# 00C-001.net
KiCad netlist of a schematic drawn in EAGLE
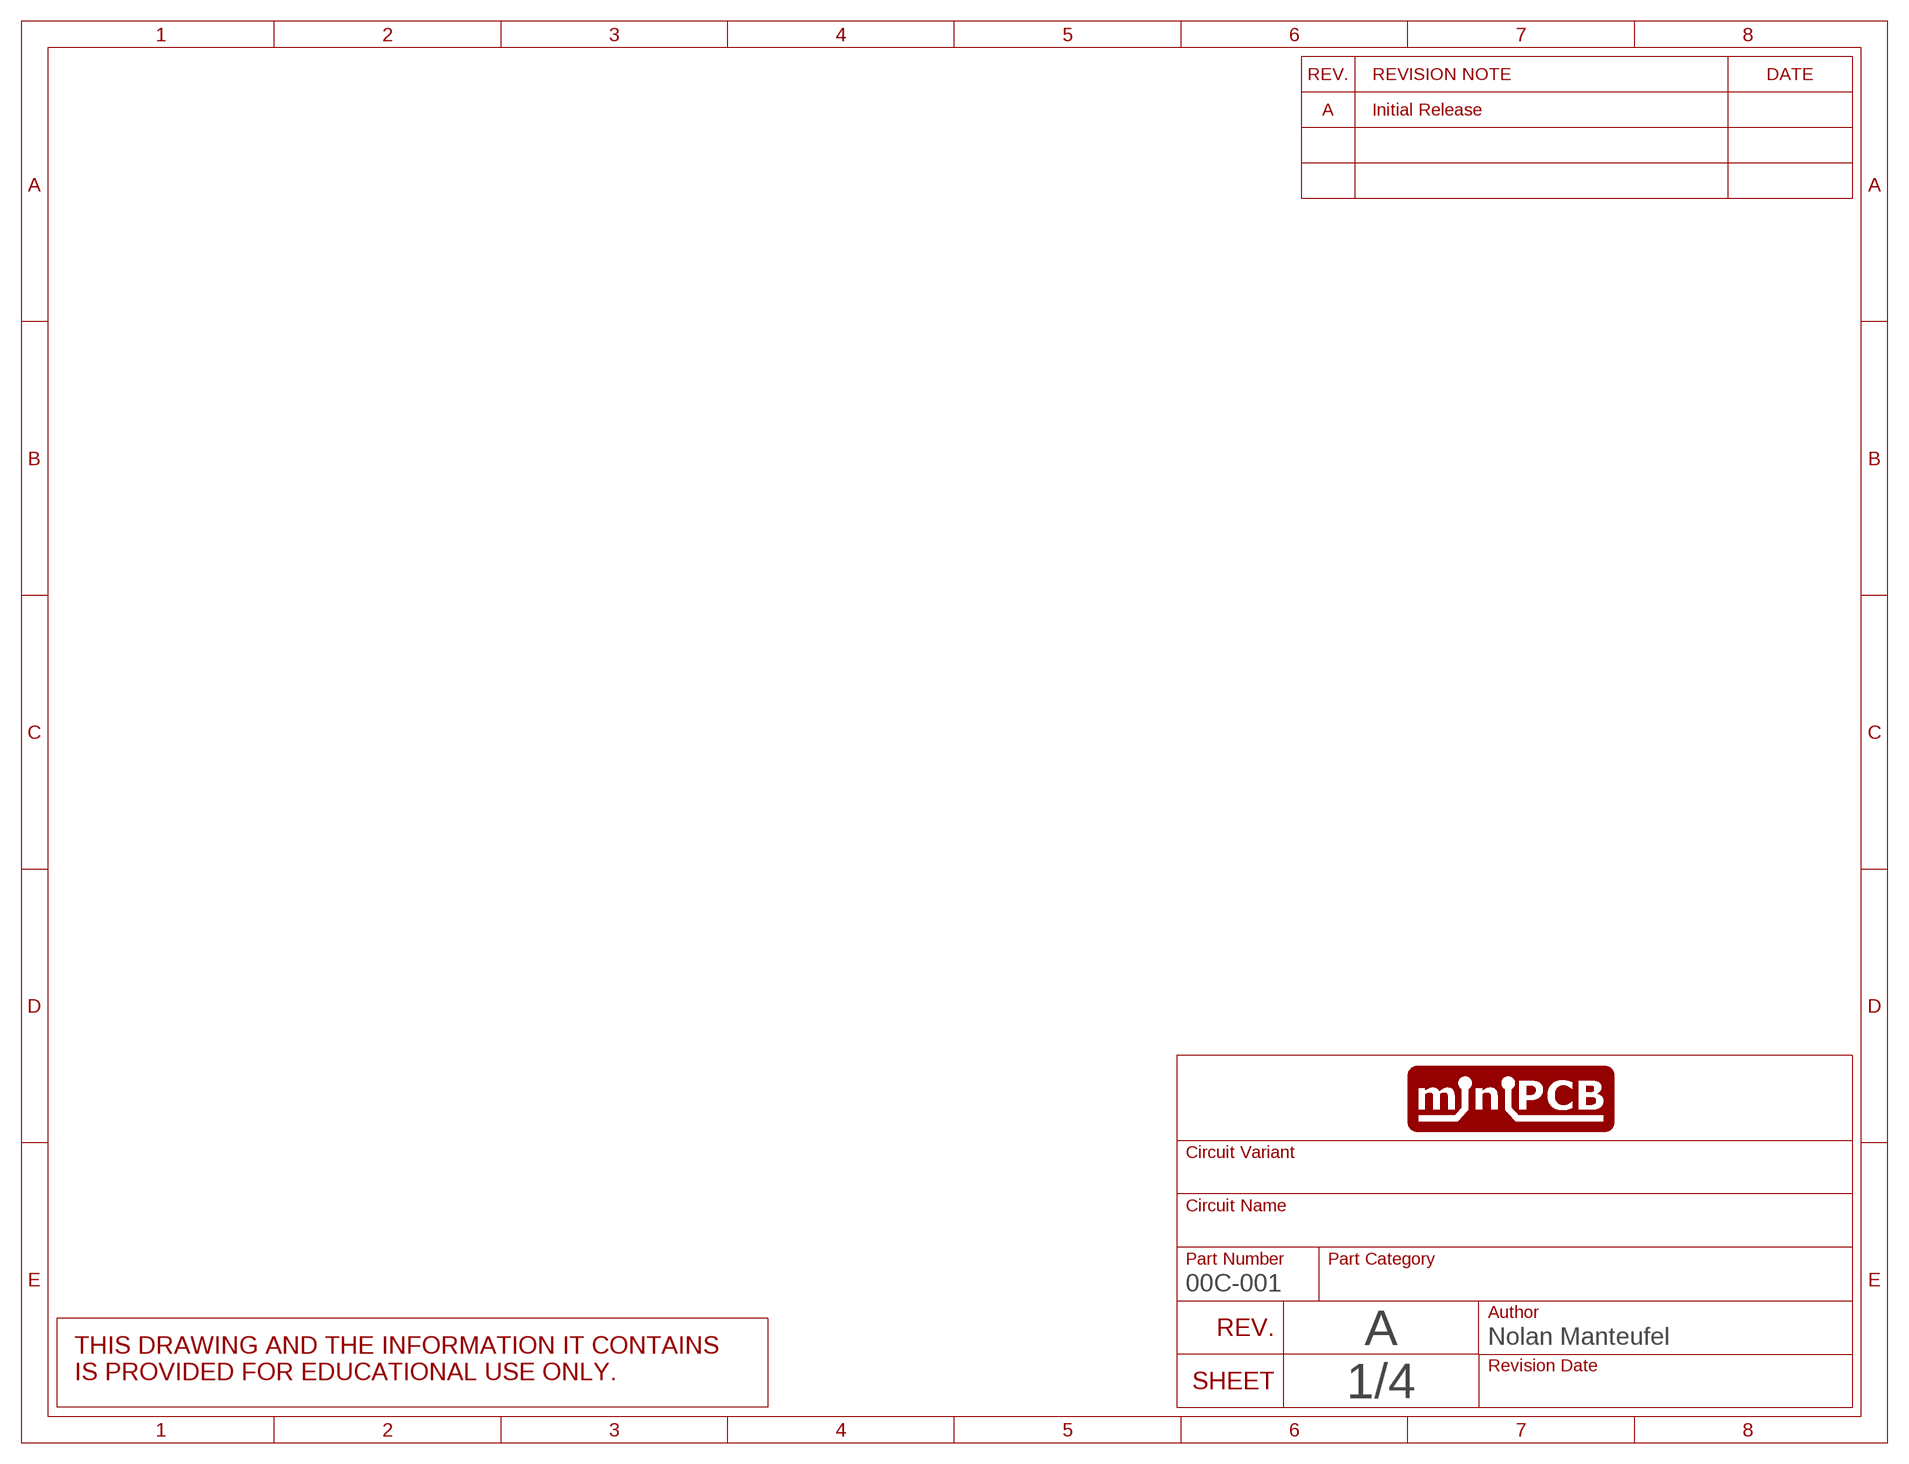
[diagram p0: schematic, sheet 1]
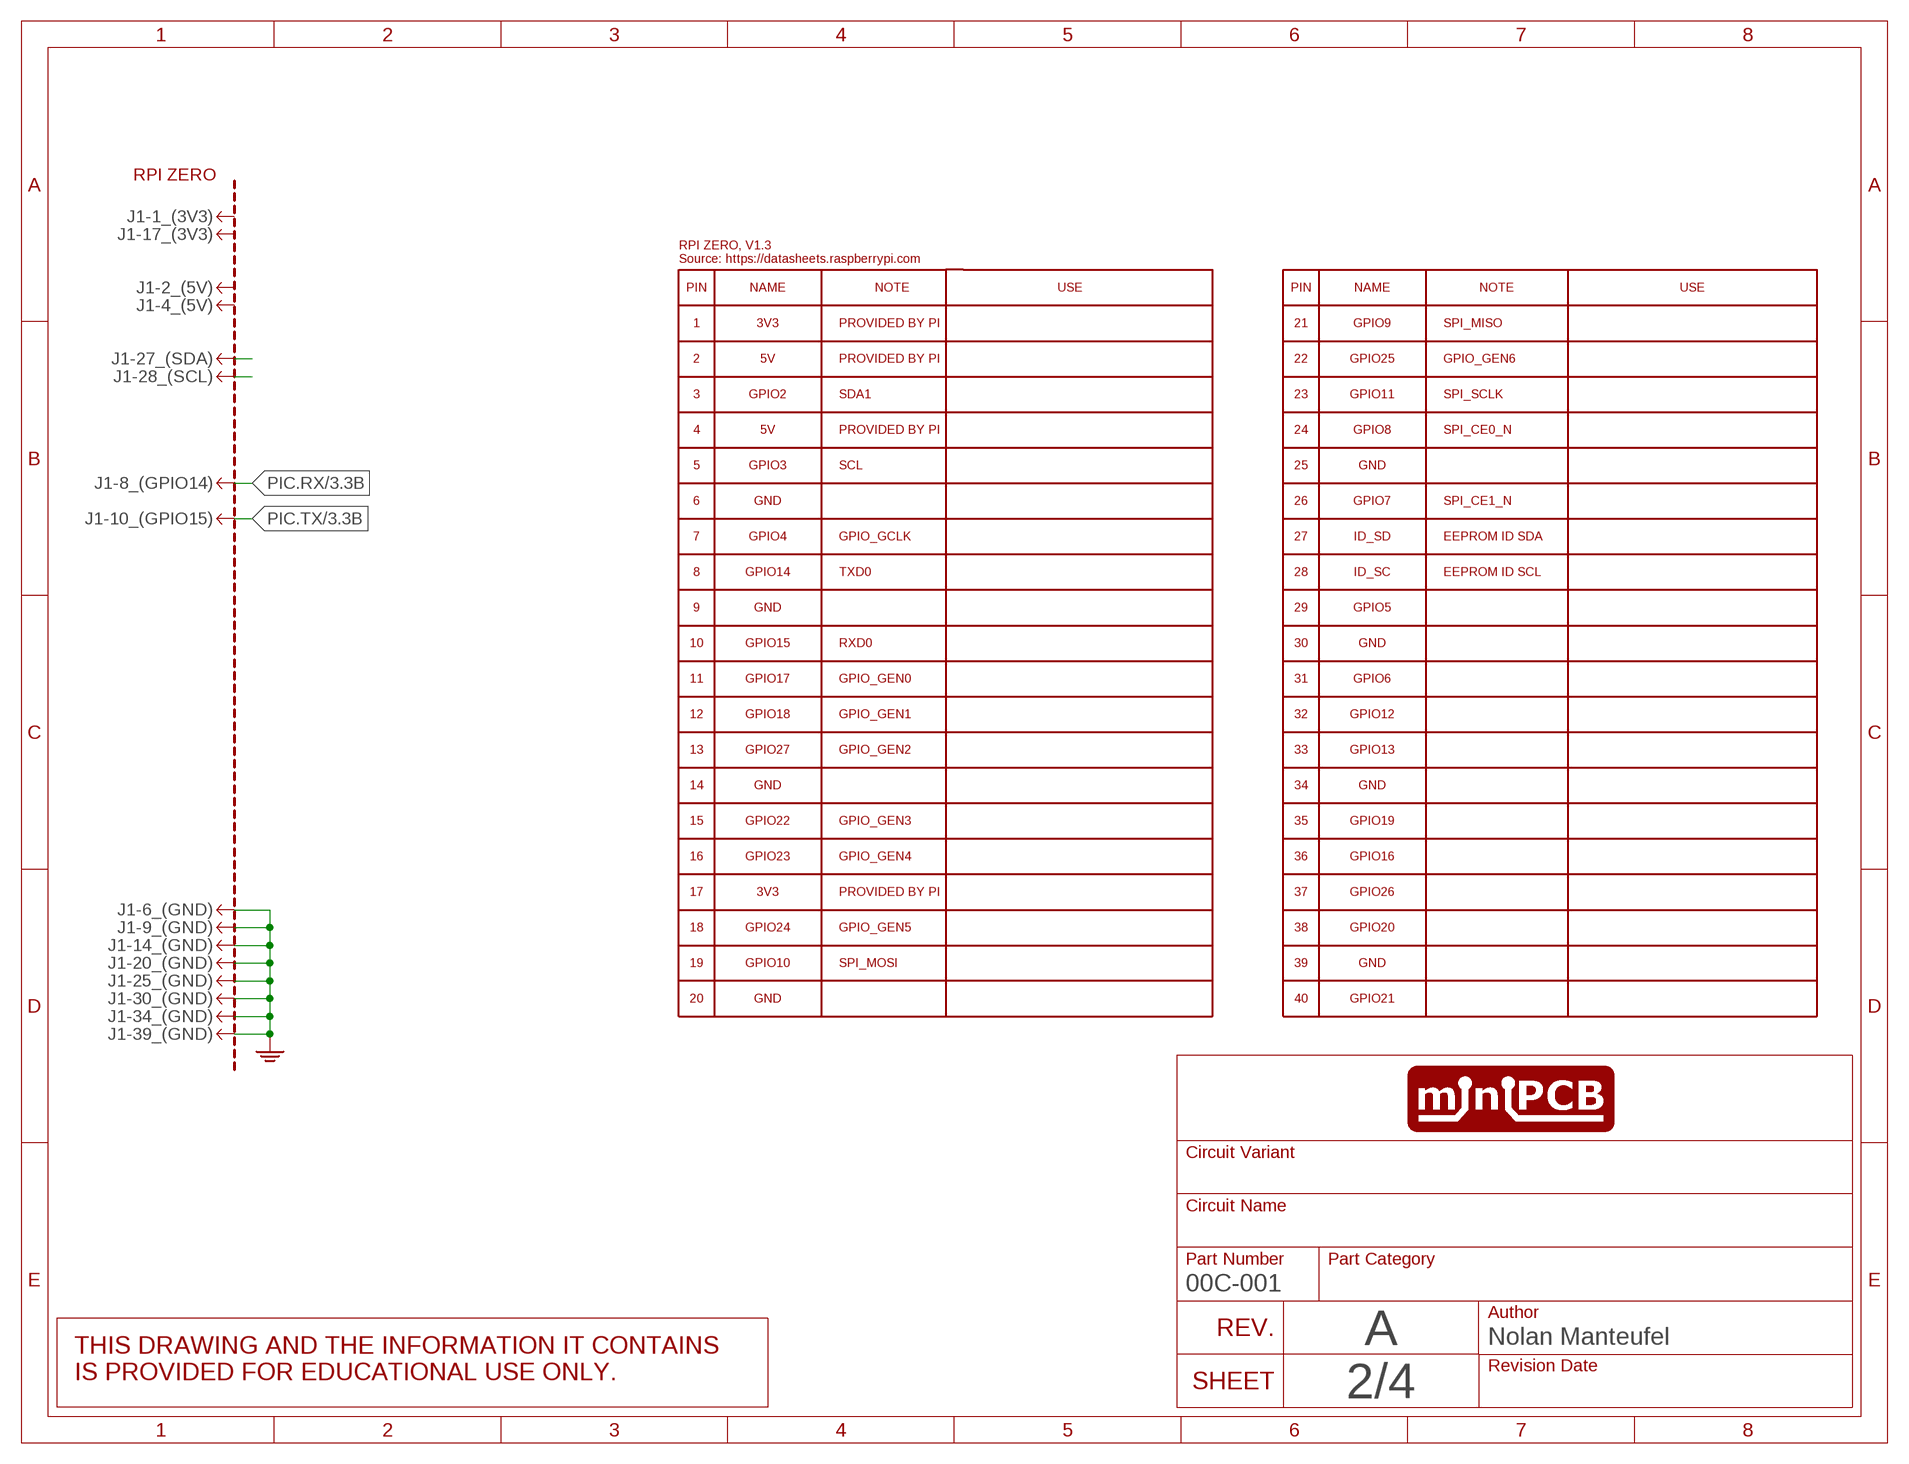
[diagram p1: schematic, sheet 2]
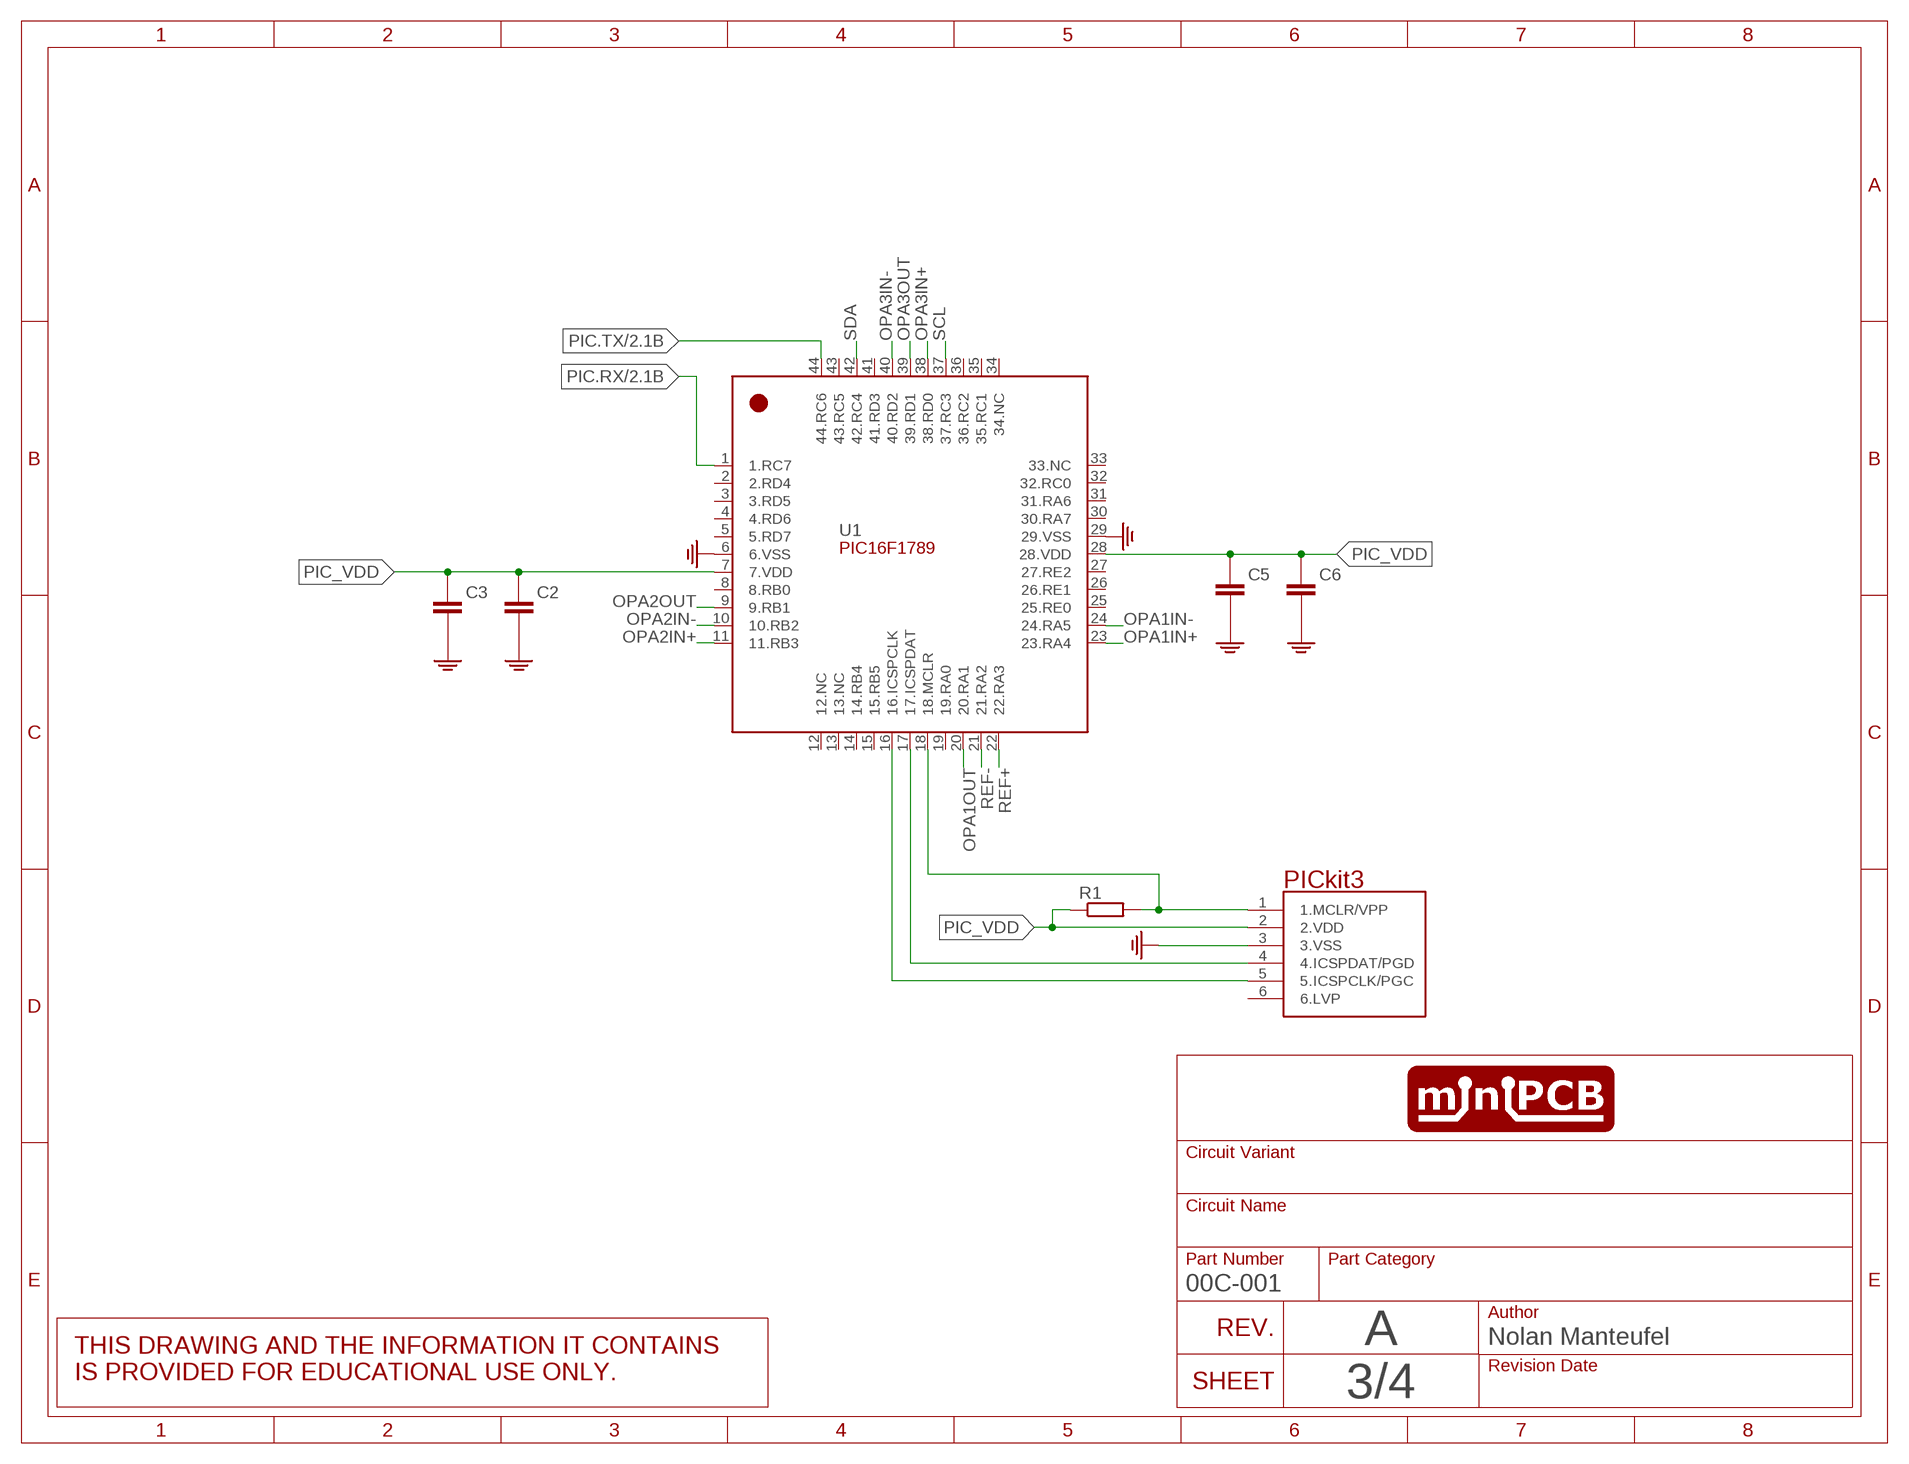
[diagram p2: schematic, sheet 3]
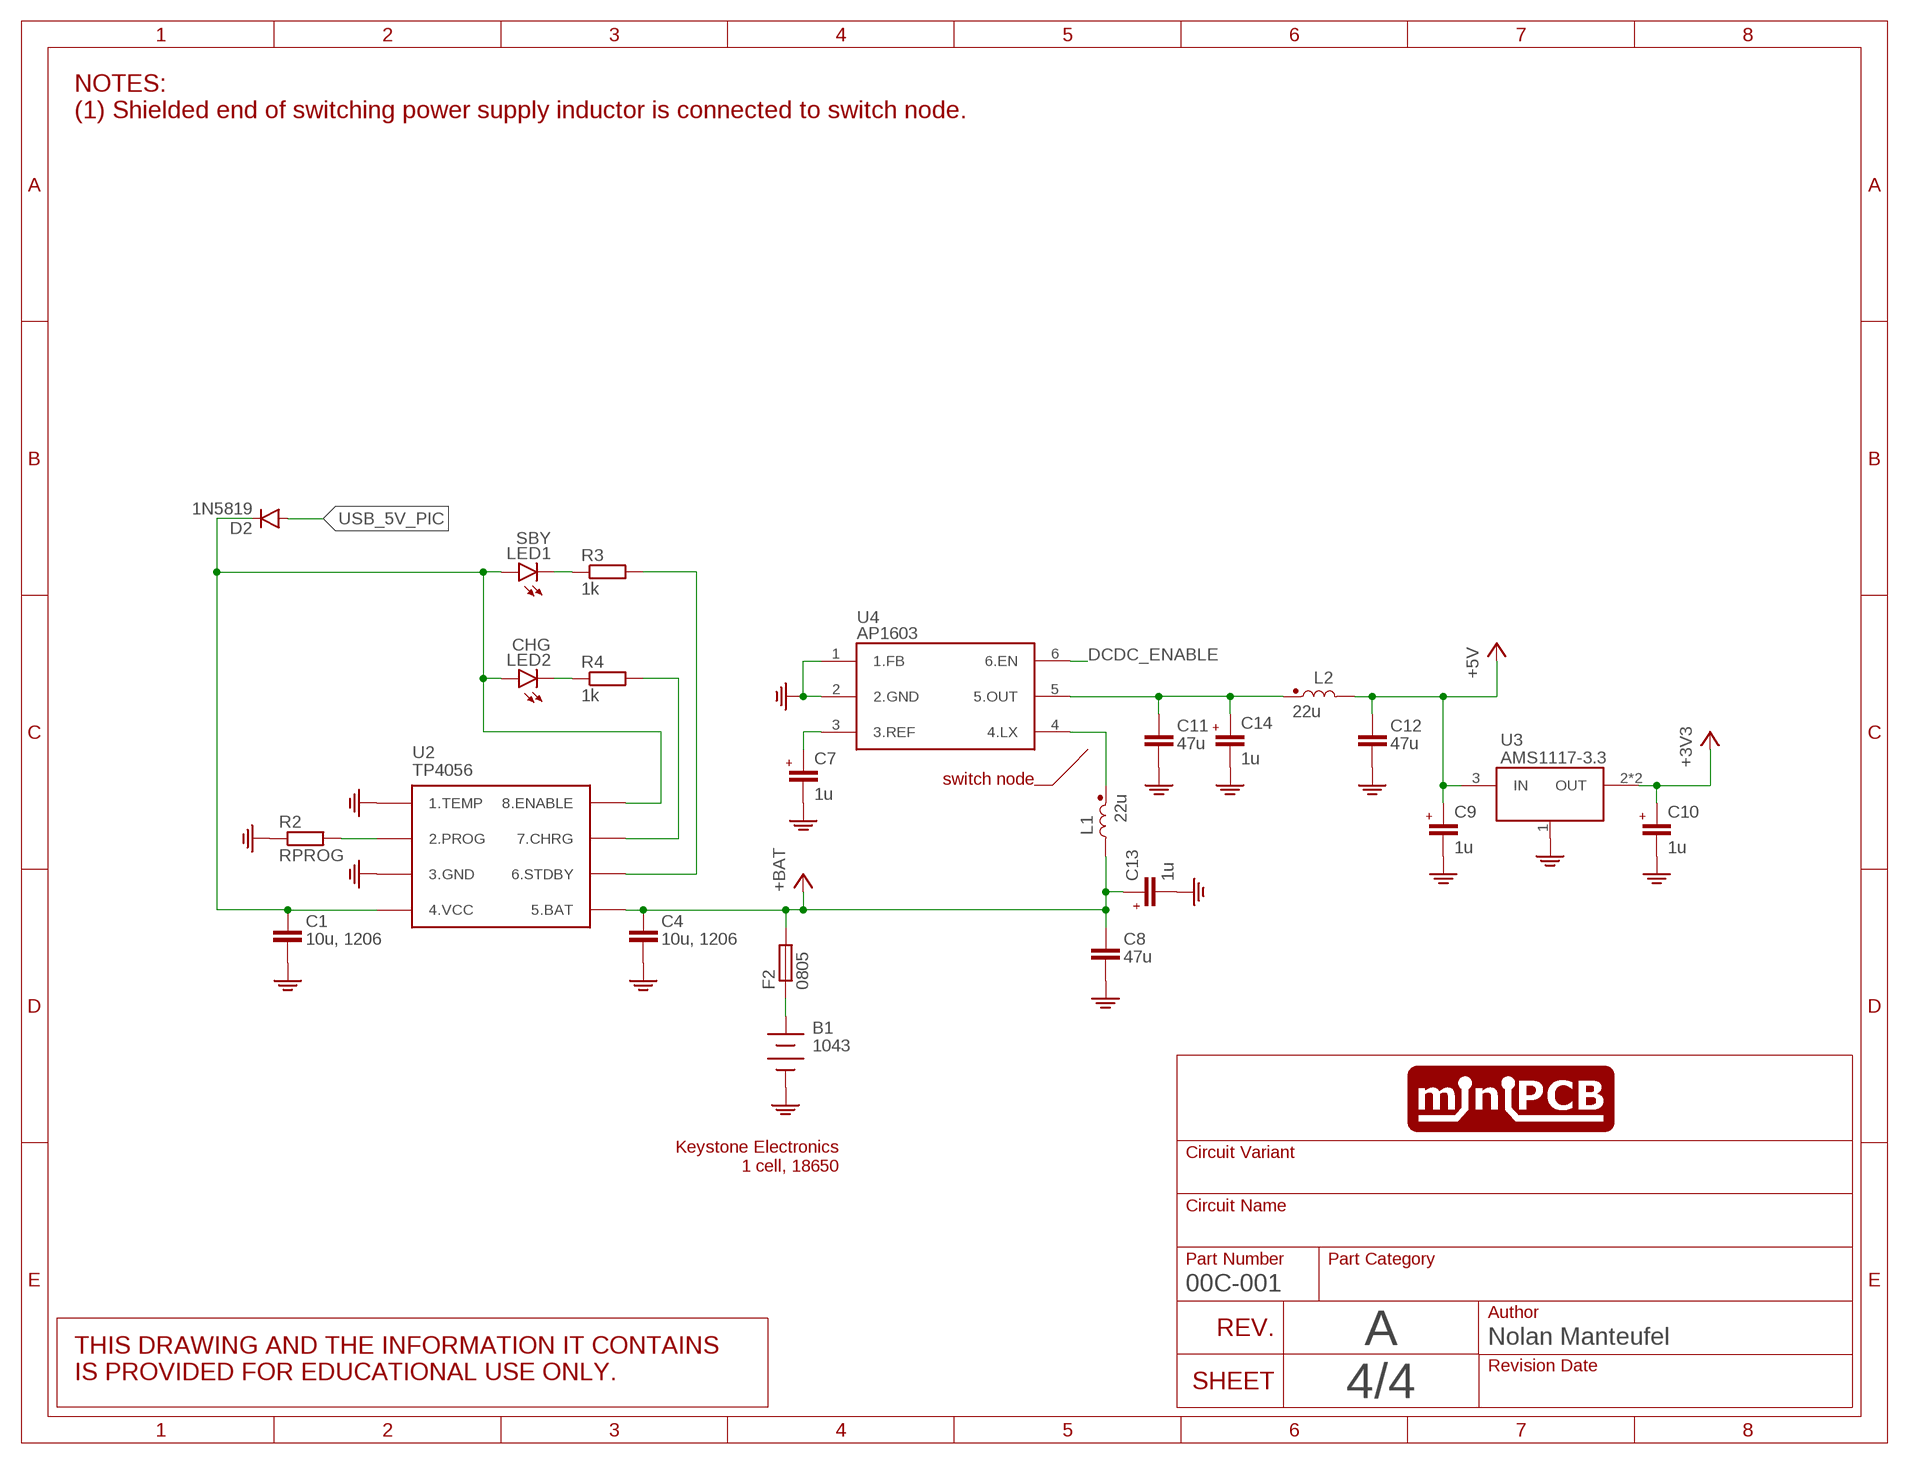
[diagram p3: schematic, sheet 4]

(export (version "E")
  (design (tool "Eeschema 10.0.6"))
  (components
    (comp (ref "C2")
      (value "CAPACITORSMD")
      (footprint "eagle-import:C0805")
      (libsource (lib "eagle-import") (part "CAPACITORSMD"))
    )
    (comp (ref "C3")
      (value "CAPACITORSMD")
      (footprint "eagle-import:C0805")
      (libsource (lib "eagle-import") (part "CAPACITORSMD"))
    )
    (comp (ref "C5")
      (value "CAPACITORSMD")
      (footprint "eagle-import:C0805")
      (libsource (lib "eagle-import") (part "CAPACITORSMD"))
    )
    (comp (ref "C6")
      (value "CAPACITORSMD")
      (footprint "eagle-import:C0805")
      (libsource (lib "eagle-import") (part "CAPACITORSMD"))
    )
    (comp (ref "R1")
      (value "RESISTORSMD")
      (footprint "eagle-import:R0805")
      (libsource (lib "eagle-import") (part "RESISTORSMD"))
    )
    (comp (ref "U$401")
      (value "PICKIT3")
      (footprint "eagle-import:PINS_6_PICKIT3")
      (libsource (lib "eagle-import") (part "PICKIT3"))
    )
    (comp (ref "U1")
      (value "PIC16F1789")
      (footprint "eagle-import:SQFP-S-10X10-44")
      (libsource (lib "eagle-import") (part "PIC16F1789"))
    )
    (comp (ref "B1")
      (value "1043")
      (footprint "eagle-import:BATTERY-18650-1")
      (libsource (lib "eagle-import") (part "BATTERY18650"))
    )
    (comp (ref "C1")
      (value "10u, 1206")
      (footprint "eagle-import:C1206")
      (libsource (lib "eagle-import") (part "C-EUC1206"))
    )
    (comp (ref "C4")
      (value "10u, 1206")
      (footprint "eagle-import:C1206")
      (libsource (lib "eagle-import") (part "C-EUC1206"))
    )
    (comp (ref "C7")
      (value "1u")
      (footprint "eagle-import:C0805")
      (libsource (lib "eagle-import") (part "C0805"))
    )
    (comp (ref "C8")
      (value "47u")
      (footprint "eagle-import:C-WE-5MM")
      (libsource (lib "eagle-import") (part "C-EU865080642006"))
    )
    (comp (ref "C9")
      (value "1u")
      (footprint "eagle-import:C0805")
      (libsource (lib "eagle-import") (part "C0805"))
    )
    (comp (ref "C10")
      (value "1u")
      (footprint "eagle-import:C0805")
      (libsource (lib "eagle-import") (part "C0805"))
    )
    (comp (ref "C11")
      (value "47u")
      (footprint "eagle-import:C-WE-5MM")
      (libsource (lib "eagle-import") (part "C-EU865080642006"))
    )
    (comp (ref "C12")
      (value "47u")
      (footprint "eagle-import:C-WE-5MM")
      (libsource (lib "eagle-import") (part "C-EU865080642006"))
    )
    (comp (ref "C13")
      (value "1u")
      (footprint "eagle-import:C0805")
      (libsource (lib "eagle-import") (part "C0805"))
    )
    (comp (ref "C14")
      (value "1u")
      (footprint "eagle-import:C0805")
      (libsource (lib "eagle-import") (part "C0805"))
    )
    (comp (ref "D2")
      (value "1N5819")
      (footprint "eagle-import:SOD80C")
      (libsource (lib "eagle-import") (part "DIODE-SOD80C"))
    )
    (comp (ref "F2")
      (value "0805")
      (footprint "eagle-import:F0805")
      (libsource (lib "eagle-import") (part "FUSE0805"))
    )
    (comp (ref "L1")
      (value "22u")
      (footprint "eagle-import:SRN5040")
      (libsource (lib "eagle-import") (part "L5040"))
    )
    (comp (ref "L2")
      (value "22u")
      (footprint "eagle-import:SRN5040")
      (libsource (lib "eagle-import") (part "L5040"))
    )
    (comp (ref "LED1")
      (value "SBY")
      (footprint "eagle-import:CHIPLED_0603")
      (libsource (lib "eagle-import") (part "LEDCHIPLED_0603"))
    )
    (comp (ref "LED2")
      (value "CHG")
      (footprint "eagle-import:CHIPLED_0603")
      (libsource (lib "eagle-import") (part "LEDCHIPLED_0603"))
    )
    (comp (ref "R2")
      (value "RPROG")
      (footprint "eagle-import:R0805")
      (libsource (lib "eagle-import") (part "R-EU__R0805"))
    )
    (comp (ref "R3")
      (value "1k")
      (footprint "eagle-import:R0805")
      (libsource (lib "eagle-import") (part "R-EU__R0805"))
    )
    (comp (ref "R4")
      (value "1k")
      (footprint "eagle-import:R0805")
      (libsource (lib "eagle-import") (part "R-EU__R0805"))
    )
    (comp (ref "U2")
      (value "TP4056")
      (footprint "eagle-import:SO08-THERMAL")
      (libsource (lib "eagle-import") (part "TP4056"))
    )
    (comp (ref "U3")
      (value "AMS1117-3.3")
      (footprint "eagle-import:SOT223")
      (libsource (lib "eagle-import") (part "REGULATOR_SCHLM1117"))
    )
    (comp (ref "U4")
      (value "AP1603")
      (footprint "eagle-import:SOT23-6")
      (libsource (lib "eagle-import") (part "AP1603"))
    )
    (comp (ref "J1-")
      (value "RPI ZERO")
      (footprint "eagle-import:RPI_ZERO")
      (libsource (lib "eagle-import") (part "RPI_ZERO"))
    )
  )
  (nets
    (net (code "1") (name "+3V3") (class "Default")
      (node (ref "C10") (pin "2") (pinfunction "+_2") (pintype "passive"))
      (node (ref "U3") (pin "2") (pinfunction "OUT_2") (pintype "bidirectional"))
      (node (ref "U3") (pin "4.TAB") (pinfunction "OUT_4.TAB") (pintype "bidirectional"))
    )
    (net (code "2") (name "+5V") (class "Default")
      (node (ref "C12") (pin "1+") (pinfunction "1_1+") (pintype "passive"))
      (node (ref "C9") (pin "2") (pinfunction "+_2") (pintype "passive"))
      (node (ref "L2") (pin "1") (pinfunction "1_1") (pintype "passive"))
      (node (ref "U3") (pin "3") (pinfunction "IN_3") (pintype "bidirectional"))
    )
    (net (code "3") (name "+BAT") (class "Default")
      (node (ref "C13") (pin "2") (pinfunction "+_2") (pintype "passive"))
      (node (ref "C4") (pin "+") (pinfunction "1_+") (pintype "passive"))
      (node (ref "C8") (pin "1+") (pinfunction "1_1+") (pintype "passive"))
      (node (ref "F2") (pin "2") (pinfunction "2_2") (pintype "passive"))
      (node (ref "L1") (pin "1") (pinfunction "1_1") (pintype "passive"))
      (node (ref "U2") (pin "5") (pinfunction "5.BAT_5") (pintype "bidirectional"))
    )
    (net (code "4") (name "DCDC_ENABLE") (class "Default")
      (node (ref "U4") (pin "6") (pinfunction "6.EN_6") (pintype "bidirectional"))
    )
    (net (code "5") (name "GND") (class "Default")
      (node (ref "B1") (pin "1") (pinfunction "-_1") (pintype "bidirectional"))
      (node (ref "C1") (pin "-") (pinfunction "2_-") (pintype "passive"))
      (node (ref "C10") (pin "1") (pinfunction "-_1") (pintype "passive"))
      (node (ref "C11") (pin "2-") (pinfunction "2_2-") (pintype "passive"))
      (node (ref "C12") (pin "2-") (pinfunction "2_2-") (pintype "passive"))
      (node (ref "C13") (pin "1") (pinfunction "-_1") (pintype "passive"))
      (node (ref "C14") (pin "1") (pinfunction "-_1") (pintype "passive"))
      (node (ref "C2") (pin "2") (pinfunction "-_2") (pintype "passive"))
      (node (ref "C3") (pin "2") (pinfunction "-_2") (pintype "passive"))
      (node (ref "C4") (pin "-") (pinfunction "2_-") (pintype "passive"))
      (node (ref "C5") (pin "2") (pinfunction "-_2") (pintype "passive"))
      (node (ref "C6") (pin "2") (pinfunction "-_2") (pintype "passive"))
      (node (ref "C7") (pin "1") (pinfunction "-_1") (pintype "passive"))
      (node (ref "C8") (pin "2-") (pinfunction "2_2-") (pintype "passive"))
      (node (ref "C9") (pin "1") (pinfunction "-_1") (pintype "passive"))
      (node (ref "J1-") (pin "14") (pinfunction "1_14") (pintype "bidirectional"))
      (node (ref "J1-") (pin "20") (pinfunction "1_20") (pintype "bidirectional"))
      (node (ref "J1-") (pin "25") (pinfunction "1_25") (pintype "bidirectional"))
      (node (ref "J1-") (pin "30") (pinfunction "1_30") (pintype "bidirectional"))
      (node (ref "J1-") (pin "34") (pinfunction "1_34") (pintype "bidirectional"))
      (node (ref "J1-") (pin "39") (pinfunction "1_39") (pintype "bidirectional"))
      (node (ref "J1-") (pin "6") (pinfunction "1_6") (pintype "bidirectional"))
      (node (ref "J1-") (pin "9") (pinfunction "1_9") (pintype "bidirectional"))
      (node (ref "R2") (pin "1") (pinfunction "1_1") (pintype "passive"))
      (node (ref "U$401") (pin "3") (pinfunction "3.VSS_3") (pintype "bidirectional"))
      (node (ref "U1") (pin "29") (pinfunction "29.VSS_29") (pintype "bidirectional"))
      (node (ref "U1") (pin "6") (pinfunction "6.VSS_6") (pintype "bidirectional"))
      (node (ref "U2") (pin "1") (pinfunction "1.TEMP_1") (pintype "bidirectional"))
      (node (ref "U2") (pin "3") (pinfunction "3.GND_3") (pintype "bidirectional"))
      (node (ref "U2") (pin "THERMAL") (pinfunction "3.GND_THERMAL") (pintype "bidirectional"))
      (node (ref "U3") (pin "1") (pinfunction "GND_1") (pintype "bidirectional"))
      (node (ref "U4") (pin "1") (pinfunction "1.FB_1") (pintype "bidirectional"))
      (node (ref "U4") (pin "2") (pinfunction "2.GND_2") (pintype "bidirectional"))
    )
    (net (code "6") (name "Net-(B1-Pad+)") (class "Default")
      (node (ref "B1") (pin "+") (pinfunction "+_+") (pintype "bidirectional"))
      (node (ref "F2") (pin "1") (pinfunction "1_1") (pintype "passive"))
    )
    (net (code "7") (name "Net-(C1-1)") (class "Default")
      (node (ref "C1") (pin "+") (pinfunction "1_+") (pintype "passive"))
      (node (ref "D2") (pin "C") (pinfunction "C_C") (pintype "passive"))
      (node (ref "LED1") (pin "A") (pinfunction "A_A") (pintype "passive"))
      (node (ref "LED2") (pin "A") (pinfunction "A_A") (pintype "passive"))
      (node (ref "U2") (pin "4") (pinfunction "4.VCC_4") (pintype "bidirectional"))
      (node (ref "U2") (pin "8") (pinfunction "8.ENABLE_8") (pintype "bidirectional"))
    )
    (net (code "8") (name "Net-(C7-+)") (class "Default")
      (node (ref "C7") (pin "2") (pinfunction "+_2") (pintype "passive"))
      (node (ref "U4") (pin "3") (pinfunction "3.REF_3") (pintype "bidirectional"))
    )
    (net (code "9") (name "Net-(C11-1)") (class "Default")
      (node (ref "C11") (pin "1+") (pinfunction "1_1+") (pintype "passive"))
      (node (ref "C14") (pin "2") (pinfunction "+_2") (pintype "passive"))
      (node (ref "L2") (pin "2") (pinfunction "2_2") (pintype "passive"))
      (node (ref "U4") (pin "5") (pinfunction "5.OUT_5") (pintype "bidirectional"))
    )
    (net (code "10") (name "Net-(LED1-PadC)") (class "Default")
      (node (ref "LED1") (pin "C") (pinfunction "C_C") (pintype "passive"))
      (node (ref "R3") (pin "1") (pinfunction "1_1") (pintype "passive"))
    )
    (net (code "11") (name "Net-(LED2-PadC)") (class "Default")
      (node (ref "LED2") (pin "C") (pinfunction "C_C") (pintype "passive"))
      (node (ref "R4") (pin "1") (pinfunction "1_1") (pintype "passive"))
    )
    (net (code "12") (name "Net-(U$401-1.MCLR{slash}VPP)") (class "Default")
      (node (ref "R1") (pin "2") (pinfunction "2_2") (pintype "passive"))
      (node (ref "U$401") (pin "1") (pinfunction "1.MCLR/VPP_1") (pintype "bidirectional"))
      (node (ref "U1") (pin "18") (pinfunction "18.MCLR_18") (pintype "bidirectional"))
    )
    (net (code "13") (name "Net-(U$401-4.ICSPDAT{slash}PGD)") (class "Default")
      (node (ref "U$401") (pin "4") (pinfunction "4.ICSPDAT/PGD_4") (pintype "bidirectional"))
      (node (ref "U1") (pin "17") (pinfunction "17.ICSPDAT_17") (pintype "bidirectional"))
    )
    (net (code "14") (name "Net-(U$401-5.ICSPCLK{slash}PGC)") (class "Default")
      (node (ref "U$401") (pin "5") (pinfunction "5.ICSPCLK/PGC_5") (pintype "bidirectional"))
      (node (ref "U1") (pin "16") (pinfunction "16.ICSPCLK_16") (pintype "bidirectional"))
    )
    (net (code "15") (name "Net-(U2-2.PROG)") (class "Default")
      (node (ref "R2") (pin "2") (pinfunction "2_2") (pintype "passive"))
      (node (ref "U2") (pin "2") (pinfunction "2.PROG_2") (pintype "bidirectional"))
    )
    (net (code "16") (name "Net-(U2-6.STDBY)") (class "Default")
      (node (ref "R3") (pin "2") (pinfunction "2_2") (pintype "passive"))
      (node (ref "U2") (pin "6") (pinfunction "6.STDBY_6") (pintype "bidirectional"))
    )
    (net (code "17") (name "Net-(U2-7.CHRG)") (class "Default")
      (node (ref "R4") (pin "2") (pinfunction "2_2") (pintype "passive"))
      (node (ref "U2") (pin "7") (pinfunction "7.CHRG_7") (pintype "bidirectional"))
    )
    (net (code "18") (name "Net-(U4-4.LX)") (class "Default")
      (node (ref "L1") (pin "2") (pinfunction "2_2") (pintype "passive"))
      (node (ref "U4") (pin "4") (pinfunction "4.LX_4") (pintype "bidirectional"))
    )
    (net (code "19") (name "OPA1IN+") (class "Default")
      (node (ref "U1") (pin "23") (pinfunction "23.RA4_23") (pintype "bidirectional"))
    )
    (net (code "20") (name "OPA1IN-") (class "Default")
      (node (ref "U1") (pin "24") (pinfunction "24.RA5_24") (pintype "bidirectional"))
    )
    (net (code "21") (name "OPA1OUT") (class "Default")
      (node (ref "U1") (pin "20") (pinfunction "20.RA1_20") (pintype "bidirectional"))
    )
    (net (code "22") (name "OPA2IN+") (class "Default")
      (node (ref "U1") (pin "11") (pinfunction "11.RB3_11") (pintype "bidirectional"))
    )
    (net (code "23") (name "OPA2IN-") (class "Default")
      (node (ref "U1") (pin "10") (pinfunction "10.RB2_10") (pintype "bidirectional"))
    )
    (net (code "24") (name "OPA2OUT") (class "Default")
      (node (ref "U1") (pin "9") (pinfunction "9.RB1_9") (pintype "bidirectional"))
    )
    (net (code "25") (name "OPA3IN+") (class "Default")
      (node (ref "U1") (pin "38") (pinfunction "38.RD0_38") (pintype "bidirectional"))
    )
    (net (code "26") (name "OPA3IN-") (class "Default")
      (node (ref "U1") (pin "40") (pinfunction "40.RD2_40") (pintype "bidirectional"))
    )
    (net (code "27") (name "OPA3OUT") (class "Default")
      (node (ref "U1") (pin "39") (pinfunction "39.RD1_39") (pintype "bidirectional"))
    )
    (net (code "28") (name "PIC.RX") (class "Default")
      (node (ref "J1-") (pin "8") (pinfunction "1_8") (pintype "bidirectional"))
      (node (ref "U1") (pin "1") (pinfunction "1.RC7_1") (pintype "bidirectional"))
    )
    (net (code "29") (name "PIC.TX") (class "Default")
      (node (ref "J1-") (pin "10") (pinfunction "1_10") (pintype "bidirectional"))
      (node (ref "U1") (pin "44") (pinfunction "44.RC6_44") (pintype "bidirectional"))
    )
    (net (code "30") (name "PIC_VDD") (class "Default")
      (node (ref "C2") (pin "1") (pinfunction "+_1") (pintype "passive"))
      (node (ref "C3") (pin "1") (pinfunction "+_1") (pintype "passive"))
      (node (ref "C5") (pin "1") (pinfunction "+_1") (pintype "passive"))
      (node (ref "C6") (pin "1") (pinfunction "+_1") (pintype "passive"))
      (node (ref "R1") (pin "1") (pinfunction "1_1") (pintype "passive"))
      (node (ref "U$401") (pin "2") (pinfunction "2.VDD_2") (pintype "bidirectional"))
      (node (ref "U1") (pin "28") (pinfunction "28.VDD_28") (pintype "bidirectional"))
      (node (ref "U1") (pin "7") (pinfunction "7.VDD_7") (pintype "bidirectional"))
    )
    (net (code "31") (name "REF+") (class "Default")
      (node (ref "U1") (pin "22") (pinfunction "22.RA3_22") (pintype "bidirectional"))
    )
    (net (code "32") (name "REF-") (class "Default")
      (node (ref "U1") (pin "21") (pinfunction "21.RA2_21") (pintype "bidirectional"))
    )
    (net (code "33") (name "SCL") (class "Default")
      (node (ref "U1") (pin "37") (pinfunction "37.RC3_37") (pintype "bidirectional"))
    )
    (net (code "34") (name "SDA") (class "Default")
      (node (ref "U1") (pin "42") (pinfunction "42.RC4_42") (pintype "bidirectional"))
    )
    (net (code "35") (name "USB_5V_PIC") (class "Default")
      (node (ref "D2") (pin "A") (pinfunction "A_A") (pintype "passive"))
    )
    (net (code "36") (name "unconnected-(J1--Pad1)") (class "Default")
      (node (ref "J1-") (pin "1") (pinfunction "1_1") (pintype "bidirectional"))
    )
    (net (code "37") (name "unconnected-(J1-AI-1-Pad4)") (class "Default")
      (node (ref "J1-") (pin "4") (pinfunction "1_4") (pintype "bidirectional"))
    )
    (net (code "38") (name "unconnected-(J1-H-1-Pad17)") (class "Default")
      (node (ref "J1-") (pin "17") (pinfunction "1_17") (pintype "bidirectional"))
    )
    (net (code "39") (name "unconnected-(J1-S-1-Pad27)") (class "Default")
      (node (ref "J1-") (pin "27") (pinfunction "1_27") (pintype "bidirectional"))
    )
    (net (code "40") (name "unconnected-(J1-T-1-Pad28)") (class "Default")
      (node (ref "J1-") (pin "28") (pinfunction "1_28") (pintype "bidirectional"))
    )
    (net (code "41") (name "unconnected-(J1-V-1-Pad2)") (class "Default")
      (node (ref "J1-") (pin "2") (pinfunction "1_2") (pintype "bidirectional"))
    )
    (net (code "42") (name "unconnected-(U$401-6.LVP-Pad6)") (class "Default")
      (node (ref "U$401") (pin "6") (pinfunction "6.LVP_6") (pintype "bidirectional"))
    )
    (net (code "43") (name "unconnected-(U1-2.RD4-Pad2)") (class "Default")
      (node (ref "U1") (pin "2") (pinfunction "2.RD4_2") (pintype "bidirectional"))
    )
    (net (code "44") (name "unconnected-(U1-3.RD5-Pad3)") (class "Default")
      (node (ref "U1") (pin "3") (pinfunction "3.RD5_3") (pintype "bidirectional"))
    )
    (net (code "45") (name "unconnected-(U1-4.RD6-Pad4)") (class "Default")
      (node (ref "U1") (pin "4") (pinfunction "4.RD6_4") (pintype "bidirectional"))
    )
    (net (code "46") (name "unconnected-(U1-5.RD7-Pad5)") (class "Default")
      (node (ref "U1") (pin "5") (pinfunction "5.RD7_5") (pintype "bidirectional"))
    )
    (net (code "47") (name "unconnected-(U1-8.RB0-Pad8)") (class "Default")
      (node (ref "U1") (pin "8") (pinfunction "8.RB0_8") (pintype "bidirectional"))
    )
    (net (code "48") (name "unconnected-(U1-12.NC-Pad12)") (class "Default")
      (node (ref "U1") (pin "12") (pinfunction "12.NC_12") (pintype "bidirectional"))
    )
    (net (code "49") (name "unconnected-(U1-13.NC-Pad13)") (class "Default")
      (node (ref "U1") (pin "13") (pinfunction "13.NC_13") (pintype "bidirectional"))
    )
    (net (code "50") (name "unconnected-(U1-14.RB4-Pad14)") (class "Default")
      (node (ref "U1") (pin "14") (pinfunction "14.RB4_14") (pintype "bidirectional"))
    )
    (net (code "51") (name "unconnected-(U1-15.RB5-Pad15)") (class "Default")
      (node (ref "U1") (pin "15") (pinfunction "15.RB5_15") (pintype "bidirectional"))
    )
    (net (code "52") (name "unconnected-(U1-19.RA0-Pad19)") (class "Default")
      (node (ref "U1") (pin "19") (pinfunction "19.RA0_19") (pintype "bidirectional"))
    )
    (net (code "53") (name "unconnected-(U1-25.RE0-Pad25)") (class "Default")
      (node (ref "U1") (pin "25") (pinfunction "25.RE0_25") (pintype "bidirectional"))
    )
    (net (code "54") (name "unconnected-(U1-26.RE1-Pad26)") (class "Default")
      (node (ref "U1") (pin "26") (pinfunction "26.RE1_26") (pintype "bidirectional"))
    )
    (net (code "55") (name "unconnected-(U1-27.RE2-Pad27)") (class "Default")
      (node (ref "U1") (pin "27") (pinfunction "27.RE2_27") (pintype "bidirectional"))
    )
    (net (code "56") (name "unconnected-(U1-30.RA7-Pad30)") (class "Default")
      (node (ref "U1") (pin "30") (pinfunction "30.RA7_30") (pintype "bidirectional"))
    )
    (net (code "57") (name "unconnected-(U1-31.RA6-Pad31)") (class "Default")
      (node (ref "U1") (pin "31") (pinfunction "31.RA6_31") (pintype "bidirectional"))
    )
    (net (code "58") (name "unconnected-(U1-32.RC0-Pad32)") (class "Default")
      (node (ref "U1") (pin "32") (pinfunction "32.RC0_32") (pintype "bidirectional"))
    )
    (net (code "59") (name "unconnected-(U1-33.NC-Pad33)") (class "Default")
      (node (ref "U1") (pin "33") (pinfunction "33.NC_33") (pintype "bidirectional"))
    )
    (net (code "60") (name "unconnected-(U1-34.NC-Pad34)") (class "Default")
      (node (ref "U1") (pin "34") (pinfunction "34.NC_34") (pintype "bidirectional"))
    )
    (net (code "61") (name "unconnected-(U1-35.RC1-Pad35)") (class "Default")
      (node (ref "U1") (pin "35") (pinfunction "35.RC1_35") (pintype "bidirectional"))
    )
    (net (code "62") (name "unconnected-(U1-36.RC2-Pad36)") (class "Default")
      (node (ref "U1") (pin "36") (pinfunction "36.RC2_36") (pintype "bidirectional"))
    )
    (net (code "63") (name "unconnected-(U1-41.RD3-Pad41)") (class "Default")
      (node (ref "U1") (pin "41") (pinfunction "41.RD3_41") (pintype "bidirectional"))
    )
    (net (code "64") (name "unconnected-(U1-43.RC5-Pad43)") (class "Default")
      (node (ref "U1") (pin "43") (pinfunction "43.RC5_43") (pintype "bidirectional"))
    )
  )
)
